# usbtouart.net
KiCad netlist of a schematic drawn in Altium Designer
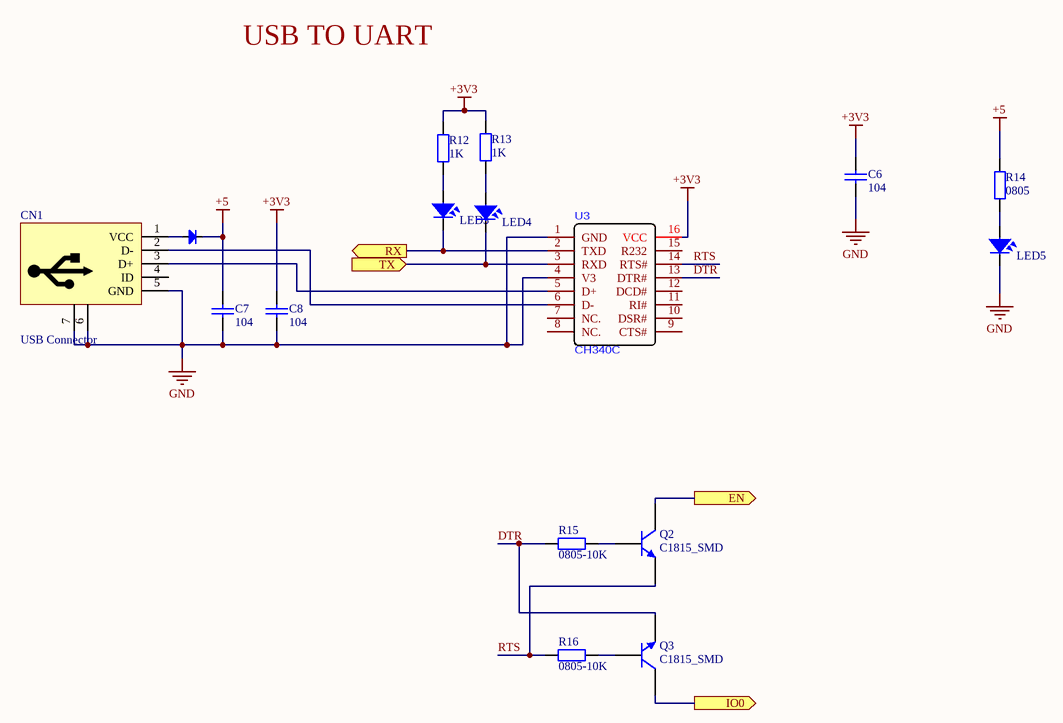
[diagram p0: usbtouart.SchDoc]

(export (version "E")
  (design (tool "Eeschema 10.0.6"))
  (components
    (comp (ref "C6")
      (value "104")
      (footprint "0805")
      (description "Capacitor (Semiconductor SIM Model)")
      (fields (field (name "PUBLISHER") "Altium Limited"))
      (libsource (lib "Altium_Devzone") (part "Cap 104_SMD"))
    )
    (comp (ref "C7")
      (value "104")
      (footprint "0805")
      (description "Capacitor (Semiconductor SIM Model)")
      (fields (field (name "PUBLISHER") "Altium Limited"))
      (libsource (lib "Altium_Devzone") (part "Cap 104_SMD"))
    )
    (comp (ref "C8")
      (value "104")
      (footprint "0805")
      (description "Capacitor (Semiconductor SIM Model)")
      (fields (field (name "PUBLISHER") "Altium Limited"))
      (libsource (lib "Altium_Devzone") (part "Cap 104_SMD"))
    )
    (comp (ref "CN1")
      (value "USB Connector")
      (footprint "MinhTien_PcbLib:USB-B-Micro-Hole")
      (libsource (lib "MinhTien_SCHLib") (part "USB_MICRO_TYPE_B"))
    )
    (comp (ref "DIO1")
      (value "Diode SMD")
      (footprint "DIO-SMD-106")
      (description "Default Diode")
      (fields (field (name "PUBLISHER") "Altium Limited"))
      (libsource (lib "Altium_Devzone") (part "Diode SMD"))
    )
    (comp (ref "LED3")
      (value "LED")
      (footprint "LED-0805-Red")
      (libsource (lib "Altium_Devzone") (part "LED SMD"))
    )
    (comp (ref "LED4")
      (value "LED")
      (footprint "LED-0805-Red")
      (libsource (lib "Altium_Devzone") (part "LED SMD"))
    )
    (comp (ref "LED5")
      (value "LED")
      (footprint "LED-0805-Orange")
      (libsource (lib "Altium_Devzone") (part "LED SMD"))
    )
    (comp (ref "Q2")
      (value "C1815_SMD")
      (footprint "MinhTien_PcbLib:SOT23")
      (description "NPN General Purpose Amplifier")
      (fields (field (name "PUBLISHER") "Altium Limited"))
      (libsource (lib "MinhTien_SCHLib") (part "C1815_SMD"))
    )
    (comp (ref "Q3")
      (value "C1815_SMD")
      (footprint "MinhTien_PcbLib:SOT23")
      (description "NPN General Purpose Amplifier")
      (fields (field (name "PUBLISHER") "Altium Limited"))
      (libsource (lib "MinhTien_SCHLib") (part "C1815_SMD"))
    )
    (comp (ref "R12")
      (value "1K")
      (footprint "DIEN TRO 0805")
      (description "Resistor SMD 0805")
      (fields (field (name "Comment") "R0805") (field (name "PUBLISHER") "Altium Limited"))
      (libsource (lib "") (part "R0805_1"))
    )
    (comp (ref "R13")
      (value "1K")
      (footprint "DIEN TRO 0805")
      (description "Resistor SMD 0805")
      (fields (field (name "Comment") "R0805") (field (name "PUBLISHER") "Altium Limited"))
      (libsource (lib "") (part "R0805_1"))
    )
    (comp (ref "R14")
      (value "0805")
      (footprint "DIEN TRO 0805")
      (description "Resistor SMD 0805")
      (fields (field (name "Comment") "R0805") (field (name "PUBLISHER") "Altium Limited"))
      (libsource (lib "") (part "R0805_1"))
    )
    (comp (ref "R15")
      (value "0805-10K")
      (footprint "DIEN TRO 0805")
      (description "Resistor SMD 0805")
      (fields (field (name "Comment") "R0805") (field (name "PUBLISHER") "Altium Limited"))
      (libsource (lib "Altium_Devzone") (part "R0805"))
    )
    (comp (ref "R16")
      (value "0805-10K")
      (footprint "DIEN TRO 0805")
      (description "Resistor SMD 0805")
      (fields (field (name "Comment") "R0805") (field (name "PUBLISHER") "Altium Limited"))
      (libsource (lib "Altium_Devzone") (part "R0805"))
    )
    (comp (ref "U3")
      (value "CH340C")
      (footprint "SOP-16_L10.0-W3.9-P1.27-LS6.0-BL")
      (libsource (lib "thuviencuazit") (part "CH340C"))
    )
  )
  (nets
    (net (code "1") (name "+3V3") (class "Default")
      (node (ref "C6") (pin "2") (pintype "passive"))
      (node (ref "C8") (pin "2") (pintype "passive"))
      (node (ref "R12") (pin "2") (pinfunction "2_2") (pintype "passive"))
      (node (ref "R13") (pin "2") (pinfunction "2_2") (pintype "passive"))
      (node (ref "U3") (pin "16") (pinfunction "VCC_16") (pintype "passive"))
    )
    (net (code "2") (name "+5") (class "Default")
      (node (ref "C7") (pin "2") (pintype "passive"))
      (node (ref "DIO1") (pin "2") (pinfunction "K_2") (pintype "passive"))
      (node (ref "R14") (pin "2") (pinfunction "2_2") (pintype "passive"))
    )
    (net (code "3") (name "/DTR") (class "Default")
      (node (ref "Q3") (pin "2") (pinfunction "E_2") (pintype "passive"))
      (node (ref "R15") (pin "1") (pinfunction "1_1") (pintype "passive"))
      (node (ref "U3") (pin "13") (pinfunction "DTR#_13") (pintype "passive"))
    )
    (net (code "4") (name "/EN") (class "Default")
      (node (ref "Q2") (pin "3") (pinfunction "C_3") (pintype "passive"))
    )
    (net (code "5") (name "/IO0") (class "Default")
      (node (ref "Q3") (pin "3") (pinfunction "C_3") (pintype "passive"))
    )
    (net (code "6") (name "/RTS") (class "Default")
      (node (ref "Q2") (pin "2") (pinfunction "E_2") (pintype "passive"))
      (node (ref "R16") (pin "1") (pinfunction "1_1") (pintype "passive"))
      (node (ref "U3") (pin "14") (pinfunction "RTS#_14") (pintype "passive"))
    )
    (net (code "7") (name "/RX") (class "Default")
      (node (ref "LED3") (pin "2") (pinfunction "2_2") (pintype "passive"))
      (node (ref "U3") (pin "2") (pinfunction "TXD_2") (pintype "passive"))
    )
    (net (code "8") (name "/TX") (class "Default")
      (node (ref "LED4") (pin "2") (pinfunction "2_2") (pintype "passive"))
      (node (ref "U3") (pin "3") (pinfunction "RXD_3") (pintype "passive"))
    )
    (net (code "9") (name "GND") (class "Default")
      (node (ref "C6") (pin "1") (pintype "passive"))
      (node (ref "C7") (pin "1") (pintype "passive"))
      (node (ref "C8") (pin "1") (pintype "passive"))
      (node (ref "CN1") (pin "5") (pinfunction "GND_5") (pintype "passive"))
      (node (ref "CN1") (pin "6") (pinfunction "SHIELD_6") (pintype "passive"))
      (node (ref "CN1") (pin "7") (pinfunction "SHIELD_7") (pintype "power_in"))
      (node (ref "LED5") (pin "2") (pinfunction "2_2") (pintype "passive"))
      (node (ref "U3") (pin "1") (pinfunction "GND_1") (pintype "passive"))
      (node (ref "U3") (pin "4") (pinfunction "V3_4") (pintype "passive"))
    )
    (net (code "10") (name "Net-(CN1-D+)") (class "Default")
      (node (ref "CN1") (pin "3") (pinfunction "D+_3") (pintype "passive"))
      (node (ref "U3") (pin "5") (pinfunction "D+_5") (pintype "passive"))
    )
    (net (code "11") (name "Net-(CN1-D-)") (class "Default")
      (node (ref "CN1") (pin "2") (pinfunction "D-_2") (pintype "passive"))
      (node (ref "U3") (pin "6") (pinfunction "D-_6") (pintype "passive"))
    )
    (net (code "12") (name "Net-(CN1-VCC)") (class "Default")
      (node (ref "CN1") (pin "1") (pinfunction "VCC_1") (pintype "passive"))
      (node (ref "DIO1") (pin "1") (pinfunction "A_1") (pintype "passive"))
    )
    (net (code "13") (name "Net-(LED3-Pad1)") (class "Default")
      (node (ref "LED3") (pin "1") (pinfunction "1_1") (pintype "passive"))
      (node (ref "R12") (pin "1") (pinfunction "1_1") (pintype "passive"))
    )
    (net (code "14") (name "Net-(LED4-Pad1)") (class "Default")
      (node (ref "LED4") (pin "1") (pinfunction "1_1") (pintype "passive"))
      (node (ref "R13") (pin "1") (pinfunction "1_1") (pintype "passive"))
    )
    (net (code "15") (name "Net-(LED5-Pad1)") (class "Default")
      (node (ref "LED5") (pin "1") (pinfunction "1_1") (pintype "passive"))
      (node (ref "R14") (pin "1") (pinfunction "1_1") (pintype "passive"))
    )
    (net (code "16") (name "Net-(Q2-B)") (class "Default")
      (node (ref "Q2") (pin "1") (pinfunction "B_1") (pintype "passive"))
      (node (ref "R15") (pin "2") (pinfunction "2_2") (pintype "passive"))
    )
    (net (code "17") (name "Net-(Q3-B)") (class "Default")
      (node (ref "Q3") (pin "1") (pinfunction "B_1") (pintype "passive"))
      (node (ref "R16") (pin "2") (pinfunction "2_2") (pintype "passive"))
    )
    (net (code "18") (name "unconnected-(CN1-ID-Pad4)") (class "Default")
      (node (ref "CN1") (pin "4") (pinfunction "ID_4") (pintype "passive"))
    )
    (net (code "19") (name "unconnected-(U3-CTS#-Pad9)") (class "Default")
      (node (ref "U3") (pin "9") (pinfunction "CTS#_9") (pintype "passive"))
    )
    (net (code "20") (name "unconnected-(U3-DCD#-Pad12)") (class "Default")
      (node (ref "U3") (pin "12") (pinfunction "DCD#_12") (pintype "passive"))
    )
    (net (code "21") (name "unconnected-(U3-DSR#-Pad10)") (class "Default")
      (node (ref "U3") (pin "10") (pinfunction "DSR#_10") (pintype "passive"))
    )
    (net (code "22") (name "unconnected-(U3-NC.-Pad7)") (class "Default")
      (node (ref "U3") (pin "7") (pinfunction "NC._7") (pintype "passive"))
    )
    (net (code "23") (name "unconnected-(U3-NC.-Pad8)") (class "Default")
      (node (ref "U3") (pin "8") (pinfunction "NC._8") (pintype "passive"))
    )
    (net (code "24") (name "unconnected-(U3-R232-Pad15)") (class "Default")
      (node (ref "U3") (pin "15") (pinfunction "R232_15") (pintype "passive"))
    )
    (net (code "25") (name "unconnected-(U3-RI#-Pad11)") (class "Default")
      (node (ref "U3") (pin "11") (pinfunction "RI#_11") (pintype "passive"))
    )
  )
)
